# BMS_V4.net
KiCad netlist of a schematic drawn in Altium Designer
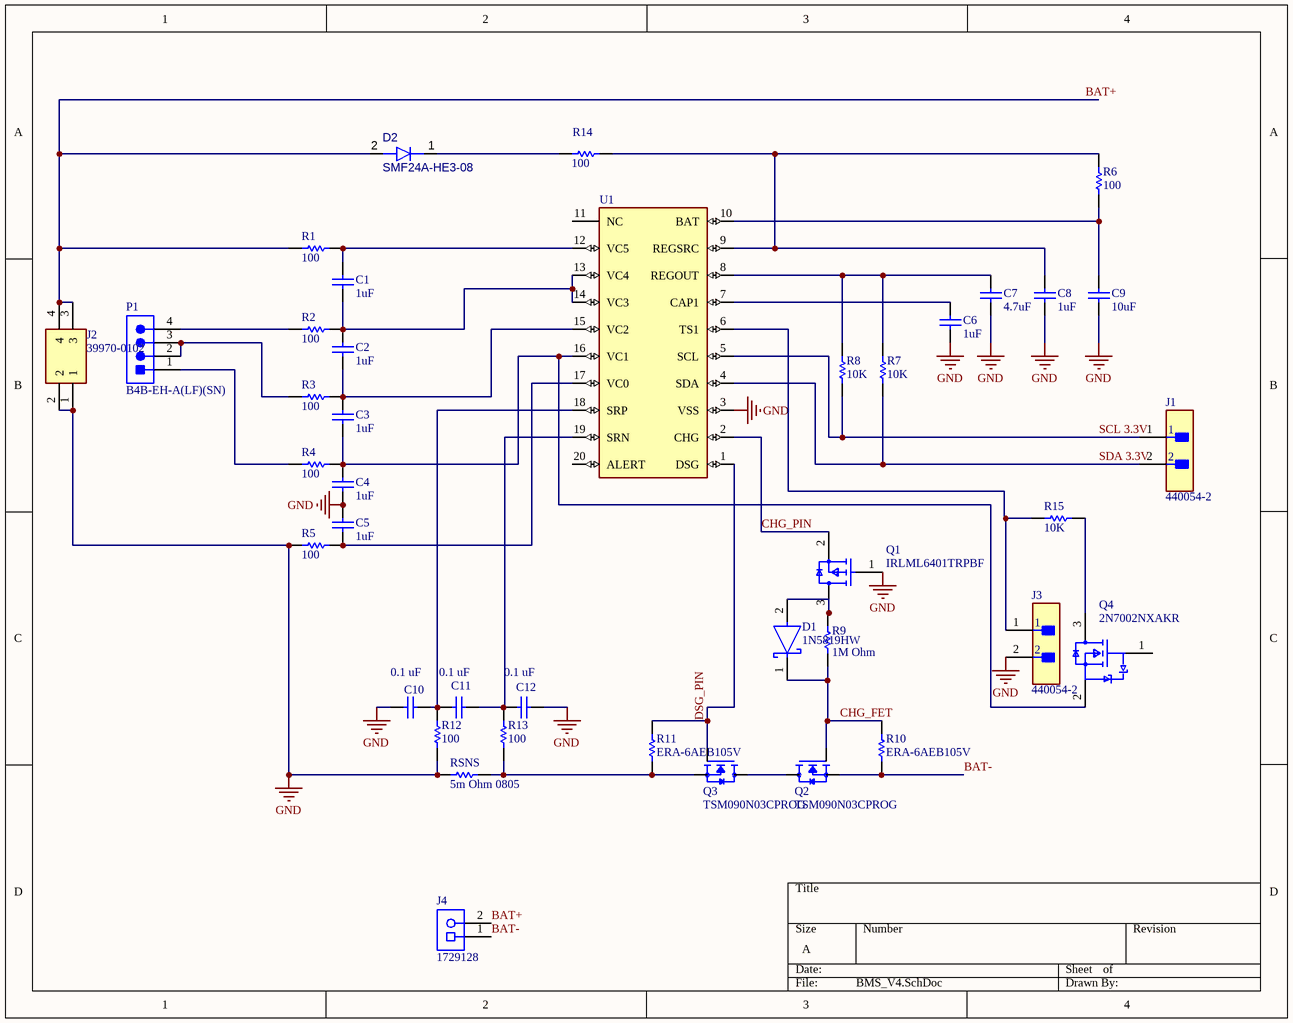
[diagram p0: BMS_V4.SchDoc]

(export (version "E")
  (design (tool "Eeschema 10.0.6"))
  (components
    (comp (ref "C1")
      (value "1uF")
      (footprint "CAPC2013X140X50LL20T25")
      (fields (field (name "PART NUMBER") "C0805C105K3RACTU") (field (name "MANUFACTURER") "Kemet"))
      (libsource (lib "Altium Content Vault") (part "CAP"))
    )
    (comp (ref "C2")
      (value "1uF")
      (footprint "CAPC2013X140X50LL20T25")
      (fields (field (name "PART NUMBER") "C0805C105K3RACTU") (field (name "MANUFACTURER") "Kemet"))
      (libsource (lib "Altium Content Vault") (part "CAP"))
    )
    (comp (ref "C3")
      (value "1uF")
      (footprint "CAPC2013X140X50LL20T25")
      (fields (field (name "PART NUMBER") "C0805C105K3RACTU") (field (name "MANUFACTURER") "Kemet"))
      (libsource (lib "Altium Content Vault") (part "CAP"))
    )
    (comp (ref "C4")
      (value "1uF")
      (footprint "CAPC2013X140X50LL20T25")
      (fields (field (name "PART NUMBER") "C0805C105K3RACTU") (field (name "MANUFACTURER") "Kemet"))
      (libsource (lib "Altium Content Vault") (part "CAP"))
    )
    (comp (ref "C5")
      (value "1uF")
      (footprint "CAPC2013X140X50LL20T25")
      (fields (field (name "PART NUMBER") "C0805C105K3RACTU") (field (name "MANUFACTURER") "Kemet"))
      (libsource (lib "Altium Content Vault") (part "CAP"))
    )
    (comp (ref "C6")
      (value "1uF")
      (footprint "CAPC2013X140X50LL20T25")
      (fields (field (name "PART NUMBER") "C0805C105K3RACTU") (field (name "MANUFACTURER") "Kemet"))
      (libsource (lib "Altium Content Vault") (part "CAP"))
    )
    (comp (ref "C7")
      (value "4.7uF")
      (footprint "CAPC2013X140X50LL20T25")
      (fields (field (name "PART NUMBER") "C0805C105K3RACTU") (field (name "MANUFACTURER") "Kemet"))
      (libsource (lib "Altium Content Vault") (part "CAP"))
    )
    (comp (ref "C8")
      (value "1uF")
      (footprint "CAPC2013X140X50LL20T25")
      (fields (field (name "PART NUMBER") "C0805C105K3RACTU") (field (name "MANUFACTURER") "Kemet"))
      (libsource (lib "Altium Content Vault") (part "CAP"))
    )
    (comp (ref "C9")
      (value "10uF")
      (footprint "CAPC2013X140X50LL20T25")
      (fields (field (name "PART NUMBER") "C0805C105K3RACTU") (field (name "MANUFACTURER") "Kemet"))
      (libsource (lib "Altium Content Vault") (part "CAP"))
    )
    (comp (ref "C10")
      (value "0.1 uF")
      (footprint "CAPC2013X140X50LL20T25")
      (fields (field (name "PART NUMBER") "C0805C105K3RACTU") (field (name "MANUFACTURER") "Kemet"))
      (libsource (lib "Altium Content Vault") (part "CAP"))
    )
    (comp (ref "C11")
      (value "0.1 uF")
      (footprint "CAPC2013X140X50LL20T25")
      (fields (field (name "PART NUMBER") "C0805C105K3RACTU") (field (name "MANUFACTURER") "Kemet"))
      (libsource (lib "Altium Content Vault") (part "CAP"))
    )
    (comp (ref "C12")
      (value "0.1 uF")
      (footprint "CAPC2013X140X50LL20T25")
      (fields (field (name "PART NUMBER") "C0805C105K3RACTU") (field (name "MANUFACTURER") "Kemet"))
      (libsource (lib "Altium Content Vault") (part "CAP"))
    )
    (comp (ref "D1")
      (value "1N5819HW")
      (footprint "FP-SOD123-IPC_A")
      (description "DIODE SCHOTTKY 40V 1A SOD123")
      (libsource (lib "Altium Content Vault") (part "1d6ec82d83fb6aee721767c19dac4b9"))
    )
    (comp (ref "D2")
      (value "SMF24A-HE3-08")
      (footprint "DIOM2818X11N")
      (description "Trans Voltage Suppressor Diode, 1000W, 24V V(RWM), Unidirectional, 1 Element, Silicon, DO-219AB")
      (libsource (lib "Dattu Hariharan") (part "DIODE-2"))
    )
    (comp (ref "J1")
      (value "440054-2")
      (footprint "FP-440054-2-MFG")
      (description "CONN HEADER VERT 2POS 2MM")
      (fields
        (field (name "MANUFACTURER") "TE Connectivity")
        (field (name "OCTOPART") "https://octopart.com/440054-2-te+connectivity-40237927")
      )
      (libsource (lib "Altium Content Vault") (part "3bc925449376181038e59eaffc5286c"))
    )
    (comp (ref "J2")
      (value "39970-0102")
      (footprint "399700102:399700102")
      (description "10.16mm Beau Eurostyle Fixed Mount PCB Terminal Block, High Power 40A,  Circuits")
      (fields (field (name "MOUSER PART NUMBER") "538-39970-0102"))
      (libsource (lib "39970-0102") (part "39970-0102"))
    )
    (comp (ref "J3")
      (value "440054-2")
      (footprint "FP-440054-2-MFG")
      (description "CONN HEADER VERT 2POS 2MM")
      (fields
        (field (name "MANUFACTURER") "TE Connectivity")
        (field (name "OCTOPART") "https://octopart.com/440054-2-te+connectivity-40237927")
      )
      (libsource (lib "Altium Content Vault") (part "3bc925449376181038e59eaffc5286c"))
    )
    (comp (ref "J4")
      (value "1729128")
      (footprint "PHOE-1729128-2_V")
      (description "PCB Terminal Block, 13.5 A, 400 V, 2-Pin THD, RoHS, Bulk")
      (fields (field (name "MANUFACTURER") "Phoenix Contact"))
      (libsource (lib "Altium Content Vault") (part "CN-2P-F-R2"))
    )
    (comp (ref "P1")
      (value "B4B-EH-A(LF)(SN)")
      (footprint "JST-B4B-EH-A_V")
      (fields (field (name "MANUFACTURER") "JST"))
      (libsource (lib "Altium Content Vault") (part "CN-1P-M-R4"))
    )
    (comp (ref "Q1")
      (value "IRLML6401TRPBF")
      (footprint "FP-SOT23-MFG")
      (description "MOSFET P-CH 12V 4.3A SOT-23")
      (fields
        (field (name "MANUFACTURER") "Infineon")
        (field (name "OCTOPART") "https://octopart.com/irlml6401trpbf-infineon-65874987")
      )
      (libsource (lib "Altium Content Vault") (part "28bfa747e7c25bfdd37193474a7f289"))
    )
    (comp (ref "Q2")
      (value "TSM090N03CPROG")
      (footprint "TRANS_TSM090N03CPROG")
      (description "N-Channel 30 V 50A (Tc) 40W (Tc) Surface Mount TO-252 (DPAK)")
      (fields (field (name "MF") "Taiwan Semiconductor"))
      (libsource (lib "Dattu Hariharan") (part "TSM090N03CPROG"))
    )
    (comp (ref "Q3")
      (value "TSM090N03CPROG")
      (footprint "TRANS_TSM090N03CPROG")
      (description "N-Channel 30 V 50A (Tc) 40W (Tc) Surface Mount TO-252 (DPAK)")
      (fields (field (name "MF") "Taiwan Semiconductor"))
      (libsource (lib "Dattu Hariharan") (part "TSM090N03CPROG"))
    )
    (comp (ref "Q4")
      (value "2N7002NXAKR")
      (footprint "FP-SOT23-IPC_B")
      (description "2N7002NXAK/SOT23/TO-236AB")
      (libsource (lib "Altium Content Vault") (part "bf18956dcdab3ff4da62eb44f668dfe"))
    )
    (comp (ref "R1")
      (value "100")
      (footprint "RESC2013X60X30ML20T20")
      (fields (field (name "PART NUMBER") "RK73H2ATTD1000F") (field (name "MANUFACTURER") "KOA Speer"))
      (libsource (lib "Altium Content Vault") (part "RES"))
    )
    (comp (ref "R2")
      (value "100")
      (footprint "RESC2013X60X30ML20T20")
      (fields (field (name "PART NUMBER") "RK73H2ATTD1000F") (field (name "MANUFACTURER") "KOA Speer"))
      (libsource (lib "Altium Content Vault") (part "RES"))
    )
    (comp (ref "R3")
      (value "100")
      (footprint "RESC2013X60X30ML20T20")
      (fields (field (name "PART NUMBER") "RK73H2ATTD1000F") (field (name "MANUFACTURER") "KOA Speer"))
      (libsource (lib "Altium Content Vault") (part "RES"))
    )
    (comp (ref "R4")
      (value "100")
      (footprint "RESC2013X60X30ML20T20")
      (fields (field (name "PART NUMBER") "RK73H2ATTD1000F") (field (name "MANUFACTURER") "KOA Speer"))
      (libsource (lib "Altium Content Vault") (part "RES"))
    )
    (comp (ref "R5")
      (value "100")
      (footprint "RESC2013X60X30ML20T20")
      (fields (field (name "PART NUMBER") "RK73H2ATTD1000F") (field (name "MANUFACTURER") "KOA Speer"))
      (libsource (lib "Altium Content Vault") (part "RES"))
    )
    (comp (ref "R6")
      (value "100")
      (footprint "RESC2013X60X30ML20T20")
      (fields (field (name "PART NUMBER") "RK73H2ATTD1000F") (field (name "MANUFACTURER") "KOA Speer"))
      (libsource (lib "Altium Content Vault") (part "RES"))
    )
    (comp (ref "R7")
      (value "10K")
      (footprint "RESC2013X60X30ML20T20")
      (fields (field (name "PART NUMBER") "RK73H2ATTD1000F") (field (name "MANUFACTURER") "KOA Speer"))
      (libsource (lib "Altium Content Vault") (part "RES"))
    )
    (comp (ref "R8")
      (value "10K")
      (footprint "RESC2013X60X30ML20T20")
      (fields (field (name "PART NUMBER") "RK73H2ATTD1000F") (field (name "MANUFACTURER") "KOA Speer"))
      (libsource (lib "Altium Content Vault") (part "RES"))
    )
    (comp (ref "R9")
      (value "1M Ohm")
      (footprint "RESC2013X60X40LL20T25")
      (fields (field (name "PART NUMBER") "ERA-6AEB105V") (field (name "MANUFACTURER") "Panasonic"))
      (libsource (lib "Altium Content Vault") (part "RES"))
    )
    (comp (ref "R10")
      (value "ERA-6AEB105V")
      (footprint "RESC2013X60X40LL20T25")
      (fields (field (name "MANUFACTURER") "Panasonic"))
      (libsource (lib "Altium Content Vault") (part "RES"))
    )
    (comp (ref "R11")
      (value "ERA-6AEB105V")
      (footprint "RESC2013X60X40LL20T25")
      (fields (field (name "MANUFACTURER") "Panasonic"))
      (libsource (lib "Altium Content Vault") (part "RES"))
    )
    (comp (ref "R12")
      (value "100")
      (footprint "RESC2013X50X30LL20T20")
      (fields (field (name "MANUFACTURER") "Vishay Dale") (field (name "PART NUMBER") "CRCW0805100RFKEA"))
      (libsource (lib "Altium Content Vault") (part "RES"))
    )
    (comp (ref "R13")
      (value "100")
      (footprint "RESC2013X50X30LL20T20")
      (fields (field (name "MANUFACTURER") "Vishay Dale") (field (name "PART NUMBER") "CRCW0805100RFKEA"))
      (libsource (lib "Altium Content Vault") (part "RES"))
    )
    (comp (ref "R14")
      (value "100")
      (footprint "RESC2013X60X30ML20T20")
      (fields (field (name "PART NUMBER") "RK73H2ATTD1000F") (field (name "MANUFACTURER") "KOA Speer"))
      (libsource (lib "Altium Content Vault") (part "RES"))
    )
    (comp (ref "R15")
      (value "10K")
      (footprint "RESC2013X60X35NL10T20")
      (description "Chip Resistor, 10 KOhm, +/- 1%, 0.125 W, -55 to 155 degC, 0805 (2012 Metric), RoHS, Tape and Reel")
      (fields (field (name "MANUFACTURER") "Yageo"))
      (libsource (lib "Altium Content Vault") (part "RES-2"))
    )
    (comp (ref "RSNS")
      (value "5m Ohm 0805")
      (footprint "RESC2013X60X30ML20T20")
      (fields (field (name "PART NUMBER") "RK73H2ATTD1000F") (field (name "MANUFACTURER") "KOA Speer"))
      (libsource (lib "Altium Content Vault") (part "RES"))
    )
    (comp (ref "U1")
      (value "~")
      (footprint "BQ7692006PW")
      (description "3 to 5-Series Cell Li-Ion and Li-Phosphate Battery Monitor (bq76940 Family)")
      (fields (field (name "MF") "Texas Instruments") (field (name "MP") "BQ7692006PW"))
      (libsource (lib "Dattu Hariharan") (part "BQ7692006PW"))
    )
  )
  (nets
    (net (code "2") (name "/BAT+") (class "Default")
      (node (ref "D2") (pin "2") (pinfunction "A_2") (pintype "passive"))
      (node (ref "J2") (pin "3") (pinfunction "3_3") (pintype "passive"))
      (node (ref "J2") (pin "4") (pinfunction "4_4") (pintype "passive"))
      (node (ref "J4") (pin "2") (pinfunction "2_2") (pintype "passive"))
      (node (ref "R1") (pin "1") (pinfunction "1_1") (pintype "passive"))
    )
    (net (code "3") (name "/BAT-") (class "Default")
      (node (ref "J4") (pin "1") (pinfunction "1_1") (pintype "passive"))
      (node (ref "Q2") (pin "3") (pinfunction "S_3") (pintype "passive"))
      (node (ref "R10") (pin "1") (pinfunction "1_1") (pintype "passive"))
    )
    (net (code "4") (name "/CHG_FET") (class "Default")
      (node (ref "D1") (pin "1") (pinfunction "C_1") (pintype "passive"))
      (node (ref "Q2") (pin "1") (pinfunction "G_1") (pintype "passive"))
      (node (ref "R10") (pin "2") (pinfunction "2_2") (pintype "passive"))
      (node (ref "R9") (pin "1") (pinfunction "1_1") (pintype "passive"))
    )
    (net (code "5") (name "/CHG_PIN") (class "Default")
      (node (ref "Q1") (pin "2") (pinfunction "S_2") (pintype "passive"))
      (node (ref "U1") (pin "2") (pinfunction "CHG_2") (pintype "bidirectional"))
    )
    (net (code "6") (name "/DSG_PIN") (class "Default")
      (node (ref "Q3") (pin "1") (pinfunction "G_1") (pintype "passive"))
      (node (ref "R11") (pin "2") (pinfunction "2_2") (pintype "passive"))
      (node (ref "U1") (pin "1") (pinfunction "DSG_1") (pintype "bidirectional"))
    )
    (net (code "7") (name "/SCL 3.3V") (class "Default")
      (node (ref "J1") (pin "1") (pinfunction "1_1") (pintype "passive"))
      (node (ref "R8") (pin "1") (pinfunction "1_1") (pintype "passive"))
      (node (ref "U1") (pin "5") (pinfunction "SCL_5") (pintype "bidirectional"))
    )
    (net (code "8") (name "/SDA 3.3V") (class "Default")
      (node (ref "J1") (pin "2") (pinfunction "2_2") (pintype "passive"))
      (node (ref "R7") (pin "1") (pinfunction "1_1") (pintype "passive"))
      (node (ref "U1") (pin "4") (pinfunction "SDA_4") (pintype "bidirectional"))
    )
    (net (code "9") (name "GND") (class "Default")
      (node (ref "C10") (pin "2") (pinfunction "2_2") (pintype "passive"))
      (node (ref "C12") (pin "1") (pinfunction "1_1") (pintype "passive"))
      (node (ref "C4") (pin "1") (pinfunction "1_1") (pintype "passive"))
      (node (ref "C5") (pin "2") (pinfunction "2_2") (pintype "passive"))
      (node (ref "C6") (pin "1") (pinfunction "1_1") (pintype "passive"))
      (node (ref "C7") (pin "1") (pinfunction "1_1") (pintype "passive"))
      (node (ref "C8") (pin "1") (pinfunction "1_1") (pintype "passive"))
      (node (ref "C9") (pin "1") (pinfunction "1_1") (pintype "passive"))
      (node (ref "J2") (pin "1") (pinfunction "1_1") (pintype "passive"))
      (node (ref "J2") (pin "2") (pinfunction "2_2") (pintype "passive"))
      (node (ref "J3") (pin "2") (pinfunction "2_2") (pintype "passive"))
      (node (ref "Q1") (pin "1") (pinfunction "G_1") (pintype "passive"))
      (node (ref "R12") (pin "1") (pinfunction "1_1") (pintype "passive"))
      (node (ref "R5") (pin "1") (pinfunction "1_1") (pintype "passive"))
      (node (ref "RSNS") (pin "2") (pinfunction "2_2") (pintype "passive"))
      (node (ref "U1") (pin "3") (pinfunction "VSS_3") (pintype "bidirectional"))
    )
    (net (code "10") (name "Net-(D1-A)") (class "Default")
      (node (ref "D1") (pin "2") (pinfunction "A_2") (pintype "passive"))
      (node (ref "Q1") (pin "3") (pinfunction "D_3") (pintype "passive"))
      (node (ref "R9") (pin "2") (pinfunction "2_2") (pintype "passive"))
    )
    (net (code "11") (name "Net-(D2-K)") (class "Default")
      (node (ref "D2") (pin "1") (pinfunction "K_1") (pintype "passive"))
      (node (ref "R14") (pin "2") (pinfunction "2_2") (pintype "passive"))
    )
    (net (code "12") (name "Net-(P1-Pad1)") (class "Default")
      (node (ref "P1") (pin "1") (pinfunction "1_1") (pintype "passive"))
      (node (ref "R4") (pin "1") (pinfunction "1_1") (pintype "passive"))
    )
    (net (code "13") (name "Net-(P1-Pad2)") (class "Default")
      (node (ref "P1") (pin "2") (pinfunction "2_2") (pintype "passive"))
      (node (ref "P1") (pin "3") (pinfunction "3_3") (pintype "passive"))
      (node (ref "R3") (pin "1") (pinfunction "1_1") (pintype "passive"))
    )
    (net (code "14") (name "Net-(P1-Pad4)") (class "Default")
      (node (ref "P1") (pin "4") (pinfunction "4_4") (pintype "passive"))
      (node (ref "R2") (pin "1") (pinfunction "1_1") (pintype "passive"))
    )
    (net (code "15") (name "Net-(Q2-D)") (class "Default")
      (node (ref "Q2") (pin "2") (pinfunction "D_2") (pintype "passive"))
      (node (ref "Q3") (pin "2") (pinfunction "D_2") (pintype "passive"))
    )
    (net (code "16") (name "Net-(Q3-S)") (class "Default")
      (node (ref "Q3") (pin "3") (pinfunction "S_3") (pintype "passive"))
      (node (ref "R11") (pin "1") (pinfunction "1_1") (pintype "passive"))
      (node (ref "R13") (pin "1") (pinfunction "1_1") (pintype "passive"))
      (node (ref "RSNS") (pin "1") (pinfunction "1_1") (pintype "passive"))
    )
    (net (code "17") (name "Net-(Q4-D)") (class "Default")
      (node (ref "Q4") (pin "3") (pinfunction "D_3") (pintype "passive"))
      (node (ref "R15") (pin "2") (pinfunction "2_2") (pintype "passive"))
    )
    (net (code "18") (name "Net-(Q4-S)") (class "Default")
      (node (ref "C3") (pin "1") (pinfunction "1_1") (pintype "passive"))
      (node (ref "C4") (pin "2") (pinfunction "2_2") (pintype "passive"))
      (node (ref "Q4") (pin "2") (pinfunction "S_2") (pintype "passive"))
      (node (ref "R4") (pin "2") (pinfunction "2_2") (pintype "passive"))
      (node (ref "U1") (pin "16") (pinfunction "VC1_16") (pintype "bidirectional"))
    )
    (net (code "19") (name "Net-(U1-BAT)") (class "Default")
      (node (ref "C9") (pin "2") (pinfunction "2_2") (pintype "passive"))
      (node (ref "R6") (pin "1") (pinfunction "1_1") (pintype "passive"))
      (node (ref "U1") (pin "10") (pinfunction "BAT_10") (pintype "bidirectional"))
    )
    (net (code "20") (name "Net-(U1-CAP1)") (class "Default")
      (node (ref "C6") (pin "2") (pinfunction "2_2") (pintype "passive"))
      (node (ref "U1") (pin "7") (pinfunction "CAP1_7") (pintype "bidirectional"))
    )
    (net (code "21") (name "Net-(U1-REGOUT)") (class "Default")
      (node (ref "C7") (pin "2") (pinfunction "2_2") (pintype "passive"))
      (node (ref "R7") (pin "2") (pinfunction "2_2") (pintype "passive"))
      (node (ref "R8") (pin "2") (pinfunction "2_2") (pintype "passive"))
      (node (ref "U1") (pin "8") (pinfunction "REGOUT_8") (pintype "bidirectional"))
    )
    (net (code "22") (name "Net-(U1-REGSRC)") (class "Default")
      (node (ref "C8") (pin "2") (pinfunction "2_2") (pintype "passive"))
      (node (ref "R14") (pin "1") (pinfunction "1_1") (pintype "passive"))
      (node (ref "R6") (pin "2") (pinfunction "2_2") (pintype "passive"))
      (node (ref "U1") (pin "9") (pinfunction "REGSRC_9") (pintype "bidirectional"))
    )
    (net (code "23") (name "Net-(U1-SRN)") (class "Default")
      (node (ref "C11") (pin "1") (pinfunction "1_1") (pintype "passive"))
      (node (ref "C12") (pin "2") (pinfunction "2_2") (pintype "passive"))
      (node (ref "R13") (pin "2") (pinfunction "2_2") (pintype "passive"))
      (node (ref "U1") (pin "19") (pinfunction "SRN_19") (pintype "bidirectional"))
    )
    (net (code "24") (name "Net-(U1-SRP)") (class "Default")
      (node (ref "C10") (pin "1") (pinfunction "1_1") (pintype "passive"))
      (node (ref "C11") (pin "2") (pinfunction "2_2") (pintype "passive"))
      (node (ref "R12") (pin "2") (pinfunction "2_2") (pintype "passive"))
      (node (ref "U1") (pin "18") (pinfunction "SRP_18") (pintype "bidirectional"))
    )
    (net (code "25") (name "Net-(U1-TS1)") (class "Default")
      (node (ref "J3") (pin "1") (pinfunction "1_1") (pintype "passive"))
      (node (ref "R15") (pin "1") (pinfunction "1_1") (pintype "passive"))
      (node (ref "U1") (pin "6") (pinfunction "TS1_6") (pintype "bidirectional"))
    )
    (net (code "26") (name "Net-(U1-VC0)") (class "Default")
      (node (ref "C5") (pin "1") (pinfunction "1_1") (pintype "passive"))
      (node (ref "R5") (pin "2") (pinfunction "2_2") (pintype "passive"))
      (node (ref "U1") (pin "17") (pinfunction "VC0_17") (pintype "bidirectional"))
    )
    (net (code "27") (name "Net-(U1-VC2)") (class "Default")
      (node (ref "C2") (pin "1") (pinfunction "1_1") (pintype "passive"))
      (node (ref "C3") (pin "2") (pinfunction "2_2") (pintype "passive"))
      (node (ref "R3") (pin "2") (pinfunction "2_2") (pintype "passive"))
      (node (ref "U1") (pin "15") (pinfunction "VC2_15") (pintype "bidirectional"))
    )
    (net (code "28") (name "Net-(U1-VC3)") (class "Default")
      (node (ref "C1") (pin "1") (pinfunction "1_1") (pintype "passive"))
      (node (ref "C2") (pin "2") (pinfunction "2_2") (pintype "passive"))
      (node (ref "R2") (pin "2") (pinfunction "2_2") (pintype "passive"))
      (node (ref "U1") (pin "13") (pinfunction "VC4_13") (pintype "bidirectional"))
      (node (ref "U1") (pin "14") (pinfunction "VC3_14") (pintype "bidirectional"))
    )
    (net (code "29") (name "Net-(U1-VC5)") (class "Default")
      (node (ref "C1") (pin "2") (pinfunction "2_2") (pintype "passive"))
      (node (ref "R1") (pin "2") (pinfunction "2_2") (pintype "passive"))
      (node (ref "U1") (pin "12") (pinfunction "VC5_12") (pintype "bidirectional"))
    )
    (net (code "30") (name "unconnected-(Q4-G-Pad1)") (class "Default")
      (node (ref "Q4") (pin "1") (pinfunction "G_1") (pintype "passive"))
    )
    (net (code "31") (name "unconnected-(U1-ALERT-Pad20)") (class "Default")
      (node (ref "U1") (pin "20") (pinfunction "ALERT_20") (pintype "bidirectional"))
    )
    (net (code "32") (name "unconnected-(U1-NC-Pad11)") (class "Default")
      (node (ref "U1") (pin "11") (pinfunction "NC_11") (pintype "passive"))
    )
  )
)
